# ECG_7_by_7.net
KiCad netlist of a schematic drawn in EAGLE
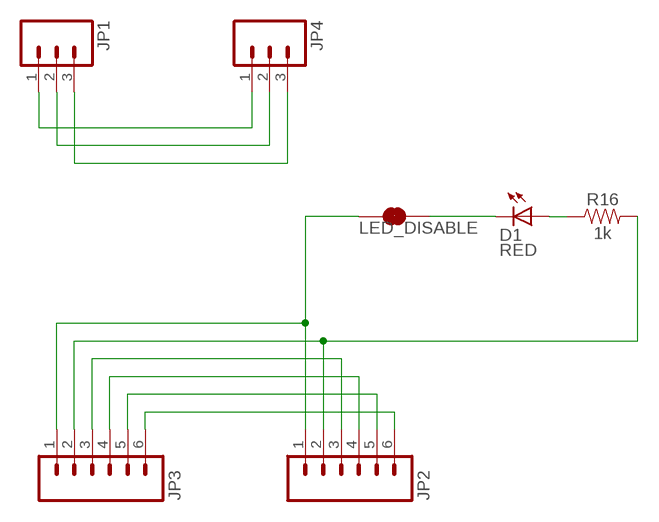
[diagram p0: schematic, sheet 1]

(export (version "E")
  (design (tool "Eeschema 10.0.6"))
  (components
    (comp (ref "D1")
      (value "RED")
      (footprint "eagle-import:LED-0603")
      (libsource (lib "eagle-import") (part "LED-RED0603"))
    )
    (comp (ref "JP1")
      (value "M03PTH")
      (footprint "eagle-import:1X03")
      (libsource (lib "eagle-import") (part "M03PTH"))
    )
    (comp (ref "JP2")
      (value "M06SIP")
      (footprint "eagle-import:1X06")
      (libsource (lib "eagle-import") (part "M06SIP"))
    )
    (comp (ref "JP3")
      (value "M06SIP")
      (footprint "eagle-import:1X06")
      (libsource (lib "eagle-import") (part "M06SIP"))
    )
    (comp (ref "JP4")
      (value "M03PTH")
      (footprint "eagle-import:1X03")
      (libsource (lib "eagle-import") (part "M03PTH"))
    )
    (comp (ref "LED_DISABLE")
      (value "JUMPER-SMT_2_NC_TRACE_SILK")
      (footprint "eagle-import:SMT-JUMPER_2_NC_TRACE_SILK")
      (libsource (lib "eagle-import") (part "JUMPER-SMT_2_NC_TRACE_SILK"))
    )
    (comp (ref "R16")
      (value "1k")
      (footprint "eagle-import:0603")
      (libsource (lib "eagle-import") (part "1KOHM-0603-1/10W-1%"))
    )
  )
  (nets
    (net (code "1") (name "Net-(D1-PadA)") (class "Default")
      (node (ref "D1") (pin "A") (pinfunction "A_A") (pintype "passive"))
      (node (ref "R16") (pin "1") (pinfunction "1_1") (pintype "passive"))
    )
    (net (code "2") (name "Net-(D1-PadC)") (class "Default")
      (node (ref "D1") (pin "C") (pinfunction "C_C") (pintype "passive"))
      (node (ref "LED_DISABLE") (pin "2") (pinfunction "2_2") (pintype "passive"))
    )
    (net (code "3") (name "Net-(JP1-Pad1)") (class "Default")
      (node (ref "JP1") (pin "1") (pinfunction "1_1") (pintype "passive"))
      (node (ref "JP4") (pin "1") (pinfunction "1_1") (pintype "passive"))
    )
    (net (code "4") (name "Net-(JP1-Pad2)") (class "Default")
      (node (ref "JP1") (pin "2") (pinfunction "2_2") (pintype "passive"))
      (node (ref "JP4") (pin "2") (pinfunction "2_2") (pintype "passive"))
    )
    (net (code "5") (name "Net-(JP1-Pad3)") (class "Default")
      (node (ref "JP1") (pin "3") (pinfunction "3_3") (pintype "passive"))
      (node (ref "JP4") (pin "3") (pinfunction "3_3") (pintype "passive"))
    )
    (net (code "6") (name "Net-(JP2-Pad1)") (class "Default")
      (node (ref "JP2") (pin "1") (pinfunction "1_1") (pintype "passive"))
      (node (ref "JP3") (pin "1") (pinfunction "1_1") (pintype "passive"))
      (node (ref "LED_DISABLE") (pin "1") (pinfunction "1_1") (pintype "passive"))
    )
    (net (code "7") (name "Net-(JP2-Pad2)") (class "Default")
      (node (ref "JP2") (pin "2") (pinfunction "2_2") (pintype "passive"))
      (node (ref "JP3") (pin "2") (pinfunction "2_2") (pintype "passive"))
      (node (ref "R16") (pin "2") (pinfunction "2_2") (pintype "passive"))
    )
    (net (code "8") (name "Net-(JP2-Pad3)") (class "Default")
      (node (ref "JP2") (pin "3") (pinfunction "3_3") (pintype "passive"))
      (node (ref "JP3") (pin "3") (pinfunction "3_3") (pintype "passive"))
    )
    (net (code "9") (name "Net-(JP2-Pad4)") (class "Default")
      (node (ref "JP2") (pin "4") (pinfunction "4_4") (pintype "passive"))
      (node (ref "JP3") (pin "4") (pinfunction "4_4") (pintype "passive"))
    )
    (net (code "10") (name "Net-(JP2-Pad5)") (class "Default")
      (node (ref "JP2") (pin "5") (pinfunction "5_5") (pintype "passive"))
      (node (ref "JP3") (pin "5") (pinfunction "5_5") (pintype "passive"))
    )
    (net (code "11") (name "Net-(JP2-Pad6)") (class "Default")
      (node (ref "JP2") (pin "6") (pinfunction "6_6") (pintype "passive"))
      (node (ref "JP3") (pin "6") (pinfunction "6_6") (pintype "passive"))
    )
  )
)
